# 3V-Switcher-50mA.net
KiCad netlist of a schematic drawn in Altium Designer
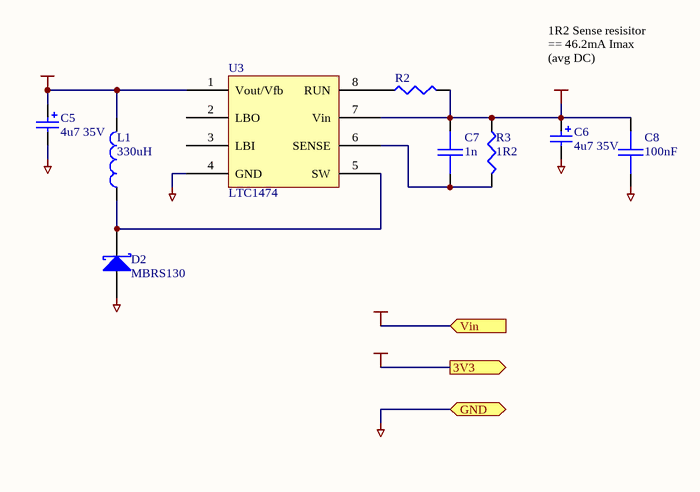
[diagram p0: 3V-Switcher-50mA.SCHDOC]

(export (version "E")
  (design (tool "Eeschema 10.0.6"))
  (components
    (comp (ref "C5")
      (value "4u7 35V")
      (footprint "MCCT-CASEC")
      (description "Polarized Capacitor (Surface Mount)")
      (libsource (lib "Miscellaneous Devices") (part "Cap Pol3"))
    )
    (comp (ref "C6")
      (value "4u7 35V")
      (footprint "MCCT-CASEC")
      (description "Polarized Capacitor (Surface Mount)")
      (libsource (lib "Miscellaneous Devices") (part "Cap Pol3"))
    )
    (comp (ref "C7")
      (value "1n")
      (footprint "0603")
      (description "Capacitor")
      (libsource (lib "Miscellaneous Devices") (part "CAP"))
    )
    (comp (ref "C8")
      (value "100nF")
      (footprint "0603")
      (description "Capacitor")
      (libsource (lib "Miscellaneous Devices") (part "CAP"))
    )
    (comp (ref "D2")
      (value "MBRS130")
      (footprint "SMB")
      (description "Schottky Diode")
      (libsource (lib "RCLDQ") (part "D SCHOTTKY"))
    )
    (comp (ref "L1")
      (value "330uH")
      (footprint "1812")
      (description "Inductor")
      (libsource (lib "Miscellaneous Devices") (part "Inductor"))
    )
    (comp (ref "R2")
      (value "100k")
      (footprint "0603")
      (description "Resistor")
      (libsource (lib "RCLDQ") (part "RES1"))
    )
    (comp (ref "R3")
      (value "1R2")
      (footprint "0603")
      (description "Resistor")
      (libsource (lib "Miscellaneous Devices") (part "RES1"))
    )
    (comp (ref "U3")
      (value "LTC1474")
      (footprint "TSOP8")
      (description "Step-down converter")
      (libsource (lib "MiscellaneousIC") (part "LTC1474"))
    )
  )
  (nets
    (net (code "1") (name "3V3") (class "Default")
      (node (ref "C5") (pin "1") (pinfunction "1_1") (pintype "passive"))
      (node (ref "L1") (pin "2") (pinfunction "2_2") (pintype "passive"))
      (node (ref "U3") (pin "1") (pinfunction "Vout/Vfb_1") (pintype "passive"))
    )
    (net (code "2") (name "GND") (class "Default")
      (node (ref "C5") (pin "2") (pinfunction "2_2") (pintype "passive"))
      (node (ref "C6") (pin "2") (pinfunction "2_2") (pintype "passive"))
      (node (ref "C8") (pin "2") (pinfunction "2_2") (pintype "passive"))
      (node (ref "D2") (pin "A") (pinfunction "A_A") (pintype "passive"))
      (node (ref "U3") (pin "4") (pinfunction "GND_4") (pintype "passive"))
    )
    (net (code "3") (name "Net-(U3-RUN)") (class "Default")
      (node (ref "R2") (pin "1") (pinfunction "1_1") (pintype "passive"))
      (node (ref "U3") (pin "8") (pinfunction "RUN_8") (pintype "passive"))
    )
    (net (code "4") (name "Net-(U3-SENSE)") (class "Default")
      (node (ref "C7") (pin "2") (pinfunction "2_2") (pintype "passive"))
      (node (ref "R3") (pin "2") (pinfunction "2_2") (pintype "passive"))
      (node (ref "U3") (pin "6") (pinfunction "SENSE_6") (pintype "passive"))
    )
    (net (code "5") (name "Net-(U3-SW)") (class "Default")
      (node (ref "D2") (pin "K") (pinfunction "K_K") (pintype "passive"))
      (node (ref "L1") (pin "1") (pinfunction "1_1") (pintype "passive"))
      (node (ref "U3") (pin "5") (pinfunction "SW_5") (pintype "passive"))
    )
    (net (code "6") (name "Vin") (class "Default")
      (node (ref "C6") (pin "1") (pinfunction "1_1") (pintype "passive"))
      (node (ref "C7") (pin "1") (pinfunction "1_1") (pintype "passive"))
      (node (ref "C8") (pin "1") (pinfunction "1_1") (pintype "passive"))
      (node (ref "R2") (pin "2") (pinfunction "2_2") (pintype "passive"))
      (node (ref "R3") (pin "1") (pinfunction "1_1") (pintype "passive"))
      (node (ref "U3") (pin "7") (pinfunction "Vin_7") (pintype "passive"))
    )
    (net (code "7") (name "unconnected-(U3-LBI-Pad3)") (class "Default")
      (node (ref "U3") (pin "3") (pinfunction "LBI_3") (pintype "passive"))
    )
    (net (code "8") (name "unconnected-(U3-LBO-Pad2)") (class "Default")
      (node (ref "U3") (pin "2") (pinfunction "LBO_2") (pintype "passive"))
    )
  )
)
